# Power.net
KiCad netlist of a schematic drawn in Altium Designer
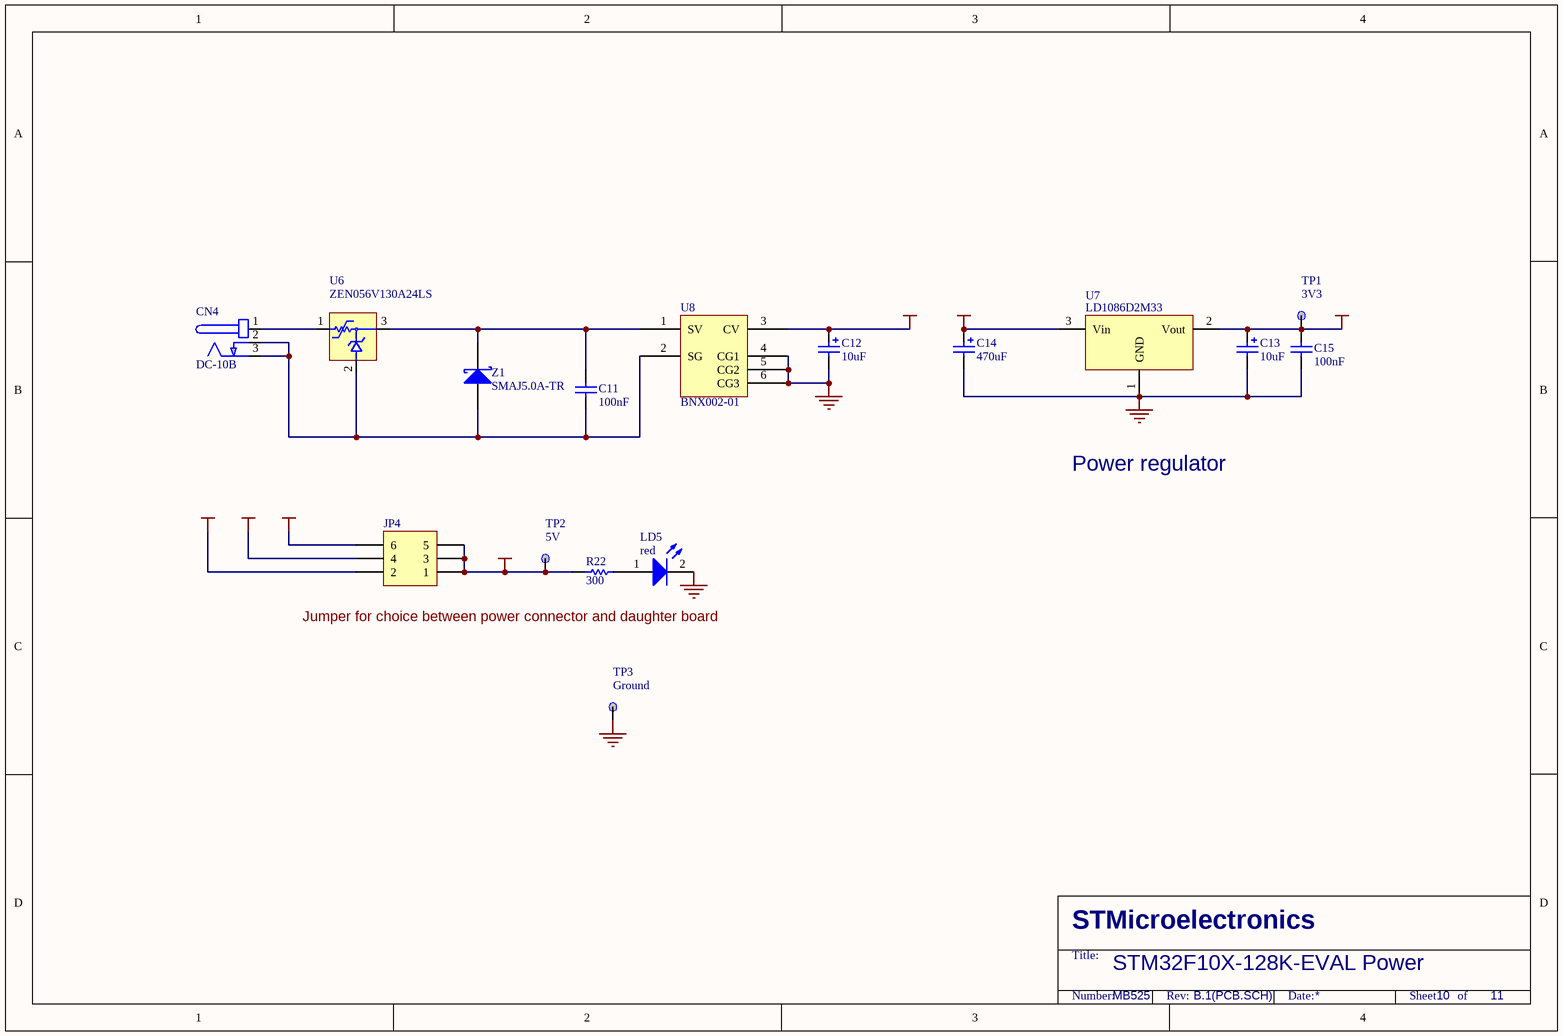
[diagram p0: Power.SchDoc]

(export (version "E")
  (design (tool "Eeschema 10.0.6"))
  (components
    (comp (ref "C11")
      (value "100nF")
      (footprint "0603P")
      (description "Capacitor")
      (fields (field (name "PUBLISHER") "Altium Limited"))
      (libsource (lib "Miscellaneous Devices") (part "CAP"))
    )
    (comp (ref "C12")
      (value "10uF")
      (footprint "C160M")
      (description "Polarized Capacitor (Radial)")
      (fields (field (name "PUBLISHER") "Altium Limited"))
      (libsource (lib "Miscellaneous Devices") (part "Cap Pol1"))
    )
    (comp (ref "C13")
      (value "10uF")
      (footprint "TAN-B")
      (description "Polarized Capacitor (Radial)")
      (fields (field (name "PUBLISHER") "Altium Limited"))
      (libsource (lib "Miscellaneous Devices") (part "Cap Pol1"))
    )
    (comp (ref "C14")
      (value "470uF")
      (footprint "C310M")
      (description "Polarized Capacitor (Radial)")
      (fields (field (name "PUBLISHER") "Altium Limited"))
      (libsource (lib "Miscellaneous Devices") (part "Cap Pol1"))
    )
    (comp (ref "C15")
      (value "100nF")
      (footprint "0603P")
      (description "Capacitor")
      (fields (field (name "PUBLISHER") "Altium Limited"))
      (libsource (lib "Miscellaneous Devices") (part "Cap"))
    )
    (comp (ref "CN4") (value "DC-10B") (footprint "DC10B") (libsource (lib "STR910_SCHLIB") (part "PJ202A")))
    (comp (ref "JP4")
      (value "~")
      (footprint "2*3P")
      (description "Header, 3-Pin, Dual row")
      (fields (field (name "PUBLISHER") "Altium Limited"))
      (libsource (lib "Miscellaneous Connectors") (part "Header 3X2"))
    )
    (comp (ref "LD5")
      (value "red")
      (footprint "D0603")
      (description "Typical RED, GREEN, YELLOW, AMBER GaAs LED")
      (fields (field (name "PUBLISHER") "Altium Limited"))
      (libsource (lib "Miscellaneous Devices") (part "LED2"))
    )
    (comp (ref "R22")
      (value "300")
      (description "Resistor")
      (fields (field (name "PUBLISHER") "Altium Limited"))
      (libsource (lib "Miscellaneous Devices") (part "res1"))
    )
    (comp (ref "TP1") (value "3V3") (footprint "TP") (libsource (lib "*") (part "TP")))
    (comp (ref "TP2") (value "5V") (footprint "TP") (libsource (lib "*") (part "TP")))
    (comp (ref "TP3") (value "Ground") (footprint "TP") (libsource (lib "*") (part "TP")))
    (comp (ref "U6")
      (value "ZEN056V130A24LS")
      (footprint "polyzen")
      (libsource (lib "STR910_SCHLIB") (part "ZEN056V130A24LS"))
    )
    (comp (ref "U7") (value "LD1086D2M33") (footprint "D2PAK/A") (libsource (lib "*") (part "VOLTREG1")))
    (comp (ref "U8")
      (value "BNX002-01")
      (footprint "BNX001")
      (libsource (lib "STR910_SCHLIB") (part "BNX002"))
    )
    (comp (ref "Z1")
      (value "SMAJ5.0A-TR")
      (footprint "1R1C")
      (description "Schottky Diode")
      (fields (field (name "PUBLISHER") "Altium Limited"))
      (libsource (lib "Miscellaneous Devices") (part "D Schottky"))
    )
  )
  (nets
    (net (code "1") (name "+3V3") (class "Default")
      (node (ref "C13") (pin "1") (pinfunction "1_1") (pintype "passive"))
      (node (ref "C15") (pin "1") (pinfunction "1_1") (pintype "passive"))
      (node (ref "TP1") (pin "1") (pinfunction "1_1") (pintype "passive"))
      (node (ref "U7") (pin "2") (pinfunction "Vout_2") (pintype "passive"))
    )
    (net (code "2") (name "+5V") (class "Default")
      (node (ref "C14") (pin "1") (pinfunction "1_1") (pintype "passive"))
      (node (ref "JP4") (pin "1") (pinfunction "1_1") (pintype "passive"))
      (node (ref "JP4") (pin "3") (pinfunction "3_3") (pintype "passive"))
      (node (ref "JP4") (pin "5") (pinfunction "5_5") (pintype "passive"))
      (node (ref "R22") (pin "2") (pinfunction "2_2") (pintype "passive"))
      (node (ref "TP2") (pin "1") (pinfunction "1_1") (pintype "passive"))
      (node (ref "U7") (pin "3") (pinfunction "Vin_3") (pintype "passive"))
    )
    (net (code "3") (name "D5V") (class "Default")
      (node (ref "JP4") (pin "4") (pinfunction "4_4") (pintype "passive"))
    )
    (net (code "4") (name "E5V") (class "Default")
      (node (ref "C12") (pin "1") (pinfunction "1_1") (pintype "passive"))
      (node (ref "JP4") (pin "6") (pinfunction "6_6") (pintype "passive"))
      (node (ref "U8") (pin "3") (pinfunction "CV_3") (pintype "passive"))
    )
    (net (code "5") (name "GND") (class "Default")
      (node (ref "C12") (pin "2") (pinfunction "2_2") (pintype "passive"))
      (node (ref "C13") (pin "2") (pinfunction "2_2") (pintype "passive"))
      (node (ref "C14") (pin "2") (pinfunction "2_2") (pintype "passive"))
      (node (ref "C15") (pin "2") (pinfunction "2_2") (pintype "passive"))
      (node (ref "LD5") (pin "2") (pinfunction "K_2") (pintype "passive"))
      (node (ref "TP3") (pin "1") (pinfunction "1_1") (pintype "passive"))
      (node (ref "U7") (pin "1") (pinfunction "GND_1") (pintype "passive"))
      (node (ref "U8") (pin "4") (pinfunction "CG1_4") (pintype "passive"))
      (node (ref "U8") (pin "5") (pinfunction "CG2_5") (pintype "passive"))
      (node (ref "U8") (pin "6") (pinfunction "CG3_6") (pintype "passive"))
    )
    (net (code "6") (name "Net-(CN4-+)") (class "Default")
      (node (ref "CN4") (pin "1") (pinfunction "+_1") (pintype "passive"))
      (node (ref "U6") (pin "1") (pintype "passive"))
    )
    (net (code "7") (name "Net-(LD5-A)") (class "Default")
      (node (ref "LD5") (pin "1") (pinfunction "A_1") (pintype "passive"))
      (node (ref "R22") (pin "1") (pinfunction "1_1") (pintype "passive"))
    )
    (net (code "8") (name "Net-(U8-SG)") (class "Default")
      (node (ref "C11") (pin "2") (pinfunction "2_2") (pintype "passive"))
      (node (ref "CN4") (pin "2") (pinfunction "GND_2") (pintype "passive"))
      (node (ref "CN4") (pin "3") (pinfunction "GND_3") (pintype "passive"))
      (node (ref "U6") (pin "2") (pintype "passive"))
      (node (ref "U8") (pin "2") (pinfunction "SG_2") (pintype "passive"))
      (node (ref "Z1") (pin "1") (pinfunction "A_1") (pintype "passive"))
    )
    (net (code "9") (name "Net-(U8-SV)") (class "Default")
      (node (ref "C11") (pin "1") (pinfunction "1_1") (pintype "passive"))
      (node (ref "U6") (pin "3") (pintype "passive"))
      (node (ref "U8") (pin "1") (pinfunction "SV_1") (pintype "passive"))
      (node (ref "Z1") (pin "2") (pinfunction "K_2") (pintype "passive"))
    )
    (net (code "10") (name "U5V") (class "Default")
      (node (ref "JP4") (pin "2") (pinfunction "2_2") (pintype "passive"))
    )
  )
)
